# ESP32.net
KiCad netlist of a schematic drawn in Altium Designer
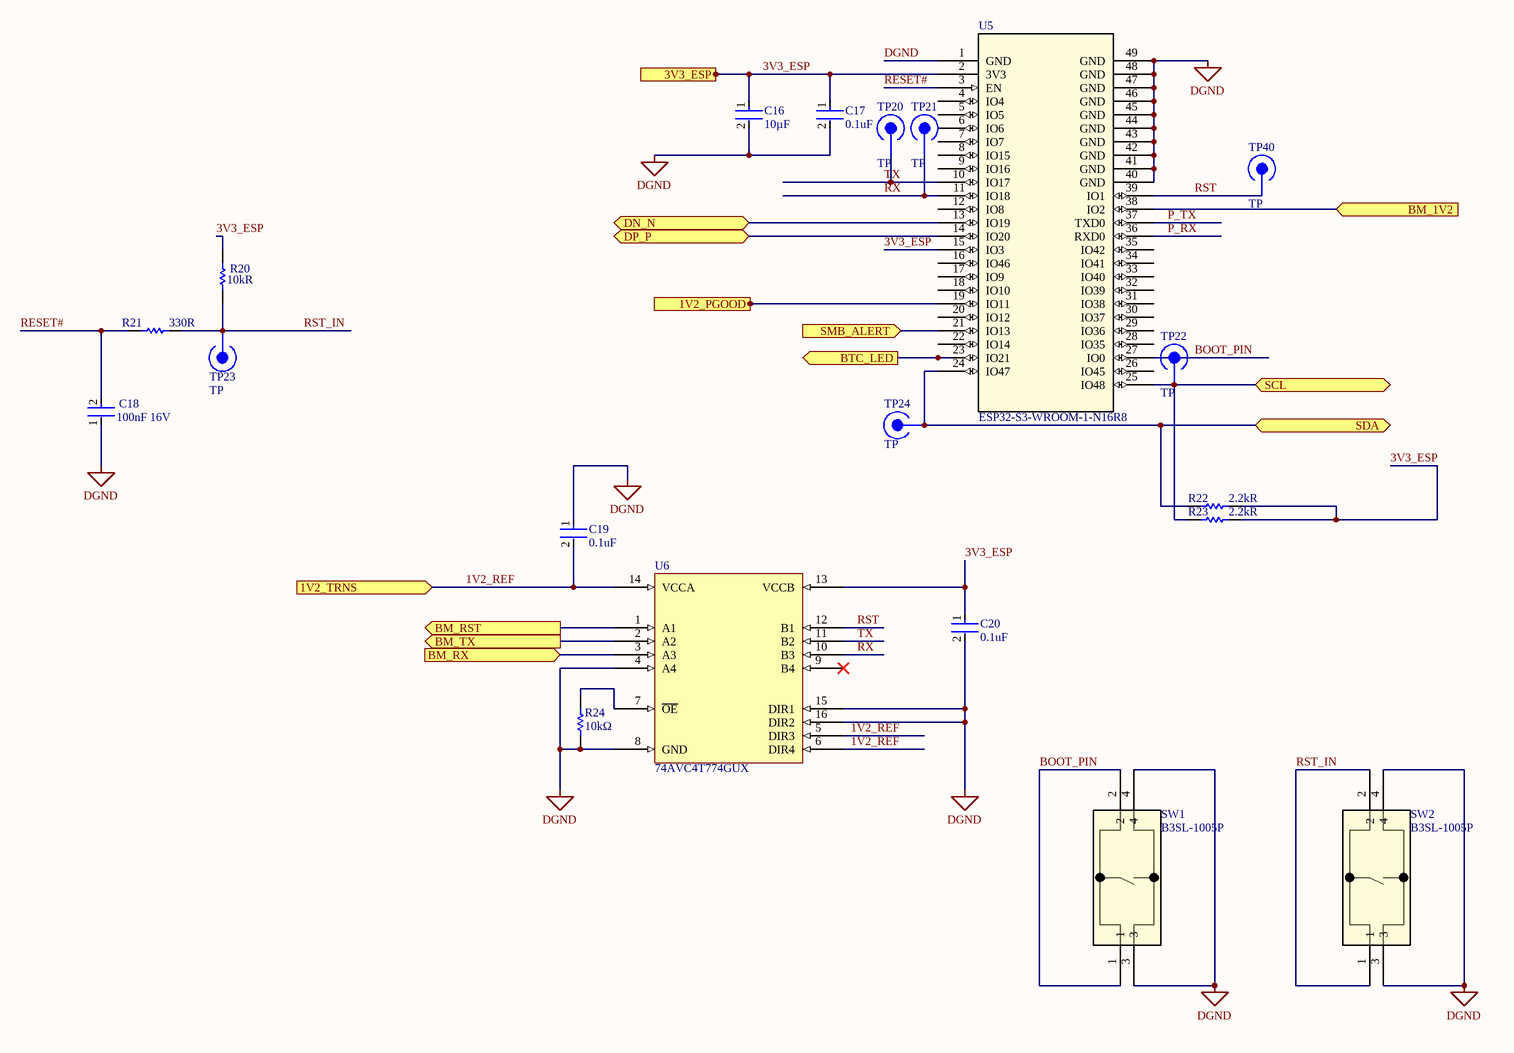
[diagram p0: ESP32.SchDoc]

(export (version "E")
  (design (tool "Eeschema 10.0.6"))
  (components
    (comp (ref "C16")
      (value "10µF")
      (footprint "FP-GRM21B-0_15-MFG")
      (fields (field (name "MANUFACTURER") "Murata") (field (name "Comment") "GRM21BR61E106KA73L"))
      (libsource (lib "Digital Shovel") (part "b4654b650e69147ec39a6b967a45e02"))
    )
    (comp (ref "C17")
      (value "0.1uF")
      (footprint "FP-CC0402-IPC_C")
      (description "Multilayer Ceramic Capacitor, 0.1 uF, 25 V, ± 10%, X7R, 0402 [1005 Metric]")
      (fields (field (name "Comment") "CC0402KRX7R7BB104"))
      (libsource (lib "Digital Shovel") (part "11868f565c42a9108669ba33697ecf6"))
    )
    (comp (ref "C18")
      (value "100nF")
      (footprint "FP-GRM15-MFG")
      (fields
        (field (name "RATING") "16V")
        (field (name "MANUFACTURER") "Murata")
        (field (name "Comment") "GRM155R71C104KA88D")
      )
      (libsource (lib "Digital Shovel") (part "CMP-00156-1"))
    )
    (comp (ref "C19")
      (value "0.1uF")
      (footprint "FP-CC0402-IPC_C")
      (description "Multilayer Ceramic Capacitor, 0.1 uF, 25 V, ± 10%, X7R, 0402 [1005 Metric]")
      (fields (field (name "Comment") "CC0402KRX7R7BB104"))
      (libsource (lib "Digital Shovel") (part "11868f565c42a9108669ba33697ecf6"))
    )
    (comp (ref "C20")
      (value "0.1uF")
      (footprint "FP-CC0402-IPC_C")
      (description "Multilayer Ceramic Capacitor, 0.1 uF, 25 V, ± 10%, X7R, 0402 [1005 Metric]")
      (fields (field (name "Comment") "CC0402KRX7R7BB104"))
      (libsource (lib "Digital Shovel") (part "11868f565c42a9108669ba33697ecf6"))
    )
    (comp (ref "R20")
      (value "10kR")
      (footprint "RESC1005X40X25LL10T10")
      (fields (field (name "Comment") "RK73H1ETTP1002F"))
      (libsource (lib "Digital Shovel") (part "RES"))
    )
    (comp (ref "R21")
      (value "330R")
      (footprint "RESC1005X40X25ML10T10")
      (fields (field (name "PART NUMBER") "RK73H1ETTP3300F") (field (name "MANUFACTURER") "KOA Speer"))
      (libsource (lib "Altium Content Vault") (part "RES"))
    )
    (comp (ref "R22")
      (value "2.2kR")
      (footprint "RESC1005X40X25NL10T10")
      (fields (field (name "MANUFACTURER") "KOA Speer") (field (name "PART NUMBER") "RK73H1ETTP2201F"))
      (libsource (lib "Altium Content Vault") (part "RES"))
    )
    (comp (ref "R23")
      (value "2.2kR")
      (footprint "RESC1005X40X25NL10T10")
      (fields (field (name "MANUFACTURER") "KOA Speer") (field (name "PART NUMBER") "RK73H1ETTP2201F"))
      (libsource (lib "Altium Content Vault") (part "RES"))
    )
    (comp (ref "R24")
      (value "10kΩ")
      (footprint "RESC1005X40X25LL10T10")
      (fields (field (name "Comment") "RK73B1ETTP103J"))
      (libsource (lib "Digital Shovel") (part "RES"))
    )
    (comp (ref "SW1")
      (value "B3SL-1005P")
      (footprint "SW_B3SL-1002P_OMR")
      (description "No Description Available")
      (libsource (lib "Digital Shovel") (part "B3SL-1005P"))
    )
    (comp (ref "SW2")
      (value "B3SL-1005P")
      (footprint "SW_B3SL-1002P_OMR")
      (description "No Description Available")
      (libsource (lib "Digital Shovel") (part "B3SL-1005P"))
    )
    (comp (ref "TP20")
      (value "TP")
      (footprint "TP-Footprint-1")
      (description "digital shovel test point")
      (libsource (lib "Digital Shovel") (part "TP-Symbol-1"))
    )
    (comp (ref "TP21")
      (value "TP")
      (footprint "TP-Footprint-1")
      (description "digital shovel test point")
      (libsource (lib "Digital Shovel") (part "TP-Symbol-1"))
    )
    (comp (ref "TP22")
      (value "TP")
      (footprint "TP-Footprint-1")
      (description "digital shovel test point")
      (libsource (lib "Digital Shovel") (part "TP-Symbol-1"))
    )
    (comp (ref "TP23")
      (value "TP")
      (footprint "TP-Footprint-1")
      (description "digital shovel test point")
      (libsource (lib "Digital Shovel") (part "TP-Symbol-1"))
    )
    (comp (ref "TP24")
      (value "TP")
      (footprint "TP-Footprint-1")
      (description "digital shovel test point")
      (libsource (lib "Digital Shovel") (part "TP-Symbol-1"))
    )
    (comp (ref "TP40")
      (value "TP")
      (footprint "TP-Footprint-1")
      (description "digital shovel test point")
      (libsource (lib "Digital Shovel") (part "TP-Symbol-1"))
    )
    (comp (ref "U5")
      (value "ESP32-S3-WROOM-1-N16R8")
      (footprint "ESP32-S3-WROOM-1-N16R8-Footprint-1")
      (description "No Description Available")
      (libsource (lib "Digital Shovel") (part "ESP32-S3-WROOM-1-N16R8"))
    )
    (comp (ref "U6")
      (value "74AVC4T774GUX")
      (footprint "74AVC4T774GUX-Footprint-1")
      (description "74AVC4T774 - 4-bit dual supply translating transceiver; 3-state")
      (fields (field (name "MANUFACTURER") "Nexperia"))
      (libsource (lib "Digital Shovel") (part "74AVC4T774GUX-Symbol-1"))
    )
  )
  (nets
    (net (code "1") (name "/1V2_PGOOD") (class "Default")
      (node (ref "U5") (pin "19") (pinfunction "IO11_19") (pintype "bidirectional"))
    )
    (net (code "2") (name "/1V2_REF") (class "Default")
      (node (ref "C19") (pin "2") (pinfunction "2_2") (pintype "passive"))
      (node (ref "U6") (pin "14") (pinfunction "VCCA_14") (pintype "input"))
      (node (ref "U6") (pin "5") (pinfunction "DIR3_5") (pintype "input"))
      (node (ref "U6") (pin "6") (pinfunction "DIR4_6") (pintype "input"))
    )
    (net (code "3") (name "/3V3_ESP") (class "Default")
      (node (ref "C16") (pin "1") (pinfunction "1_1") (pintype "passive"))
      (node (ref "C17") (pin "1") (pinfunction "1_1") (pintype "passive"))
      (node (ref "C20") (pin "1") (pinfunction "1_1") (pintype "passive"))
      (node (ref "R20") (pin "2") (pinfunction "2_2") (pintype "passive"))
      (node (ref "R22") (pin "2") (pinfunction "2_2") (pintype "passive"))
      (node (ref "R23") (pin "2") (pinfunction "2_2") (pintype "passive"))
      (node (ref "U5") (pin "15") (pinfunction "IO3_15") (pintype "bidirectional"))
      (node (ref "U5") (pin "2") (pinfunction "3V3_2") (pintype "power_in"))
      (node (ref "U6") (pin "13") (pinfunction "VCCB_13") (pintype "input"))
    )
    (net (code "4") (name "/BM_1V2") (class "Default")
      (node (ref "U5") (pin "38") (pinfunction "IO2_38") (pintype "bidirectional"))
    )
    (net (code "5") (name "/BM_RST") (class "Default")
      (node (ref "U6") (pin "1") (pinfunction "A1_1") (pintype "input"))
    )
    (net (code "6") (name "/BM_RX") (class "Default")
      (node (ref "U6") (pin "3") (pinfunction "A3_3") (pintype "input"))
    )
    (net (code "7") (name "/BM_TX") (class "Default")
      (node (ref "U6") (pin "2") (pinfunction "A2_2") (pintype "input"))
    )
    (net (code "8") (name "/BOOT_PIN") (class "Default")
      (node (ref "SW1") (pin "1") (pinfunction "1_1") (pintype "passive"))
      (node (ref "SW1") (pin "2") (pinfunction "2_2") (pintype "passive"))
      (node (ref "U5") (pin "27") (pinfunction "IO0_27") (pintype "bidirectional"))
    )
    (net (code "9") (name "/BTC_LED") (class "Default")
      (node (ref "U5") (pin "23") (pinfunction "IO21_23") (pintype "bidirectional"))
    )
    (net (code "10") (name "/DN_N") (class "Default")
      (node (ref "U5") (pin "13") (pinfunction "IO19_13") (pintype "bidirectional"))
    )
    (net (code "11") (name "/DP_P") (class "Default")
      (node (ref "U5") (pin "14") (pinfunction "IO20_14") (pintype "bidirectional"))
    )
    (net (code "12") (name "/P_RX") (class "Default")
      (node (ref "U5") (pin "36") (pinfunction "RXD0_36") (pintype "bidirectional"))
    )
    (net (code "13") (name "/P_TX") (class "Default")
      (node (ref "U5") (pin "37") (pinfunction "TXD0_37") (pintype "bidirectional"))
    )
    (net (code "14") (name "/RESET#") (class "Default")
      (node (ref "C18") (pin "2") (pinfunction "2_2") (pintype "passive"))
      (node (ref "R21") (pin "1") (pinfunction "1_1") (pintype "passive"))
      (node (ref "U5") (pin "3") (pinfunction "EN_3") (pintype "input"))
    )
    (net (code "15") (name "/RST") (class "Default")
      (node (ref "TP40") (pin "1") (pintype "passive"))
      (node (ref "U5") (pin "39") (pinfunction "IO1_39") (pintype "bidirectional"))
      (node (ref "U6") (pin "12") (pinfunction "B1_12") (pintype "input"))
    )
    (net (code "16") (name "/RST_IN") (class "Default")
      (node (ref "R20") (pin "1") (pinfunction "1_1") (pintype "passive"))
      (node (ref "R21") (pin "2") (pinfunction "2_2") (pintype "passive"))
      (node (ref "SW2") (pin "1") (pinfunction "1_1") (pintype "passive"))
      (node (ref "SW2") (pin "2") (pinfunction "2_2") (pintype "passive"))
      (node (ref "TP23") (pin "1") (pintype "passive"))
    )
    (net (code "17") (name "/RX") (class "Default")
      (node (ref "TP21") (pin "1") (pintype "passive"))
      (node (ref "U5") (pin "11") (pinfunction "IO18_11") (pintype "bidirectional"))
      (node (ref "U6") (pin "10") (pinfunction "B3_10") (pintype "input"))
    )
    (net (code "18") (name "/SCL") (class "Default")
      (node (ref "R23") (pin "1") (pinfunction "1_1") (pintype "passive"))
      (node (ref "TP22") (pin "1") (pintype "passive"))
      (node (ref "U5") (pin "25") (pinfunction "IO48_25") (pintype "bidirectional"))
    )
    (net (code "19") (name "/SDA") (class "Default")
      (node (ref "R22") (pin "1") (pinfunction "1_1") (pintype "passive"))
      (node (ref "TP24") (pin "1") (pintype "passive"))
      (node (ref "U5") (pin "24") (pinfunction "IO47_24") (pintype "bidirectional"))
    )
    (net (code "20") (name "/SMB_ALERT") (class "Default")
      (node (ref "U5") (pin "21") (pinfunction "IO13_21") (pintype "bidirectional"))
    )
    (net (code "21") (name "/TX") (class "Default")
      (node (ref "TP20") (pin "1") (pintype "passive"))
      (node (ref "U5") (pin "10") (pinfunction "IO17_10") (pintype "bidirectional"))
      (node (ref "U6") (pin "11") (pinfunction "B2_11") (pintype "input"))
    )
    (net (code "22") (name "DGND") (class "Default")
      (node (ref "C16") (pin "2") (pinfunction "2_2") (pintype "passive"))
      (node (ref "C17") (pin "2") (pinfunction "2_2") (pintype "passive"))
      (node (ref "C18") (pin "1") (pinfunction "1_1") (pintype "passive"))
      (node (ref "C19") (pin "1") (pinfunction "1_1") (pintype "passive"))
      (node (ref "C20") (pin "2") (pinfunction "2_2") (pintype "passive"))
      (node (ref "R24") (pin "2") (pinfunction "2_2") (pintype "passive"))
      (node (ref "SW1") (pin "3") (pinfunction "3_3") (pintype "passive"))
      (node (ref "SW1") (pin "4") (pinfunction "4_4") (pintype "passive"))
      (node (ref "SW2") (pin "3") (pinfunction "3_3") (pintype "passive"))
      (node (ref "SW2") (pin "4") (pinfunction "4_4") (pintype "passive"))
      (node (ref "U5") (pin "1") (pinfunction "GND_1") (pintype "power_in"))
      (node (ref "U5") (pin "40") (pinfunction "GND_40") (pintype "power_in"))
      (node (ref "U5") (pin "41") (pinfunction "GND_41") (pintype "power_in"))
      (node (ref "U5") (pin "42") (pinfunction "GND_42") (pintype "power_in"))
      (node (ref "U5") (pin "43") (pinfunction "GND_43") (pintype "power_in"))
      (node (ref "U5") (pin "44") (pinfunction "GND_44") (pintype "power_in"))
      (node (ref "U5") (pin "45") (pinfunction "GND_45") (pintype "power_in"))
      (node (ref "U5") (pin "46") (pinfunction "GND_46") (pintype "power_in"))
      (node (ref "U5") (pin "47") (pinfunction "GND_47") (pintype "power_in"))
      (node (ref "U5") (pin "48") (pinfunction "GND_48") (pintype "power_in"))
      (node (ref "U5") (pin "49") (pinfunction "GND_49") (pintype "power_in"))
      (node (ref "U6") (pin "15") (pinfunction "DIR1_15") (pintype "input"))
      (node (ref "U6") (pin "16") (pinfunction "DIR2_16") (pintype "input"))
      (node (ref "U6") (pin "4") (pinfunction "A4_4") (pintype "input"))
      (node (ref "U6") (pin "8") (pinfunction "GND_8") (pintype "input"))
    )
    (net (code "23") (name "Net-(U6-~{OE})") (class "Default")
      (node (ref "R24") (pin "1") (pinfunction "1_1") (pintype "passive"))
      (node (ref "U6") (pin "7") (pinfunction "~{OE}_7") (pintype "input"))
    )
    (net (code "24") (name "unconnected-(U5-IO4-Pad4)") (class "Default")
      (node (ref "U5") (pin "4") (pinfunction "IO4_4") (pintype "bidirectional"))
    )
    (net (code "25") (name "unconnected-(U5-IO5-Pad5)") (class "Default")
      (node (ref "U5") (pin "5") (pinfunction "IO5_5") (pintype "bidirectional"))
    )
    (net (code "26") (name "unconnected-(U5-IO6-Pad6)") (class "Default")
      (node (ref "U5") (pin "6") (pinfunction "IO6_6") (pintype "bidirectional"))
    )
    (net (code "27") (name "unconnected-(U5-IO7-Pad7)") (class "Default")
      (node (ref "U5") (pin "7") (pinfunction "IO7_7") (pintype "bidirectional"))
    )
    (net (code "28") (name "unconnected-(U5-IO8-Pad12)") (class "Default")
      (node (ref "U5") (pin "12") (pinfunction "IO8_12") (pintype "bidirectional"))
    )
    (net (code "29") (name "unconnected-(U5-IO9-Pad17)") (class "Default")
      (node (ref "U5") (pin "17") (pinfunction "IO9_17") (pintype "bidirectional"))
    )
    (net (code "30") (name "unconnected-(U5-IO10-Pad18)") (class "Default")
      (node (ref "U5") (pin "18") (pinfunction "IO10_18") (pintype "bidirectional"))
    )
    (net (code "31") (name "unconnected-(U5-IO12-Pad20)") (class "Default")
      (node (ref "U5") (pin "20") (pinfunction "IO12_20") (pintype "bidirectional"))
    )
    (net (code "32") (name "unconnected-(U5-IO14-Pad22)") (class "Default")
      (node (ref "U5") (pin "22") (pinfunction "IO14_22") (pintype "bidirectional"))
    )
    (net (code "33") (name "unconnected-(U5-IO15-Pad8)") (class "Default")
      (node (ref "U5") (pin "8") (pinfunction "IO15_8") (pintype "bidirectional"))
    )
    (net (code "34") (name "unconnected-(U5-IO16-Pad9)") (class "Default")
      (node (ref "U5") (pin "9") (pinfunction "IO16_9") (pintype "bidirectional"))
    )
    (net (code "35") (name "unconnected-(U5-IO35-Pad28)") (class "Default")
      (node (ref "U5") (pin "28") (pinfunction "IO35_28") (pintype "bidirectional"))
    )
    (net (code "36") (name "unconnected-(U5-IO36-Pad29)") (class "Default")
      (node (ref "U5") (pin "29") (pinfunction "IO36_29") (pintype "bidirectional"))
    )
    (net (code "37") (name "unconnected-(U5-IO37-Pad30)") (class "Default")
      (node (ref "U5") (pin "30") (pinfunction "IO37_30") (pintype "bidirectional"))
    )
    (net (code "38") (name "unconnected-(U5-IO38-Pad31)") (class "Default")
      (node (ref "U5") (pin "31") (pinfunction "IO38_31") (pintype "bidirectional"))
    )
    (net (code "39") (name "unconnected-(U5-IO39-Pad32)") (class "Default")
      (node (ref "U5") (pin "32") (pinfunction "IO39_32") (pintype "bidirectional"))
    )
    (net (code "40") (name "unconnected-(U5-IO40-Pad33)") (class "Default")
      (node (ref "U5") (pin "33") (pinfunction "IO40_33") (pintype "bidirectional"))
    )
    (net (code "41") (name "unconnected-(U5-IO41-Pad34)") (class "Default")
      (node (ref "U5") (pin "34") (pinfunction "IO41_34") (pintype "bidirectional"))
    )
    (net (code "42") (name "unconnected-(U5-IO42-Pad35)") (class "Default")
      (node (ref "U5") (pin "35") (pinfunction "IO42_35") (pintype "bidirectional"))
    )
    (net (code "43") (name "unconnected-(U5-IO45-Pad26)") (class "Default")
      (node (ref "U5") (pin "26") (pinfunction "IO45_26") (pintype "bidirectional"))
    )
    (net (code "44") (name "unconnected-(U5-IO46-Pad16)") (class "Default")
      (node (ref "U5") (pin "16") (pinfunction "IO46_16") (pintype "bidirectional"))
    )
    (net (code "45") (name "unconnected-(U6-B4-Pad9)") (class "Default")
      (node (ref "U6") (pin "9") (pinfunction "B4_9") (pintype "input+no_connect"))
    )
  )
)
